# final-node.net
KiCad netlist of a schematic drawn in EAGLE
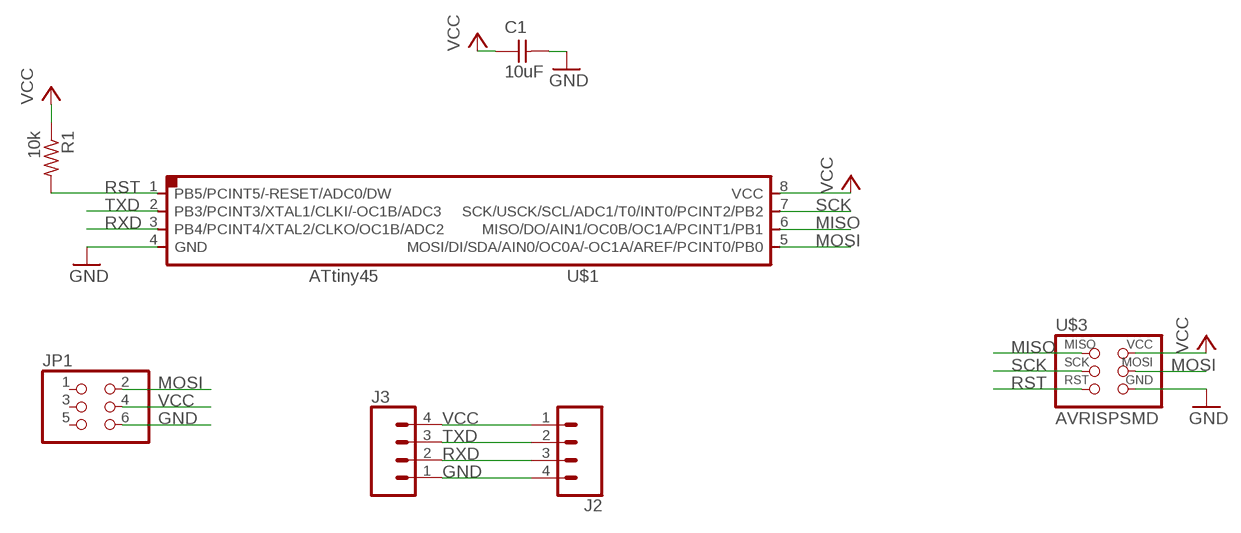
[diagram p0: schematic, sheet 1]

(export (version "E")
  (design (tool "Eeschema 10.0.6"))
  (components
    (comp (ref "C1")
      (value "10uF")
      (footprint "eagle-import:C1206FAB")
      (libsource (lib "eagle-import") (part "CAP-UNPOLARIZEDFAB"))
    )
    (comp (ref "J2")
      (value "CONN_04SMD")
      (footprint "eagle-import:1X04_SMD_RA_MALE")
      (libsource (lib "eagle-import") (part "CONN_04SMD"))
    )
    (comp (ref "J3")
      (value "CONN_04SMD")
      (footprint "eagle-import:1X04_SMD_RA_MALE")
      (libsource (lib "eagle-import") (part "CONN_04SMD"))
    )
    (comp (ref "JP1")
      (value "PINHD-2X3-SMD")
      (footprint "eagle-import:2X03SMD")
      (libsource (lib "eagle-import") (part "PINHD-2X3-SMD"))
    )
    (comp (ref "R1")
      (value "10k")
      (footprint "eagle-import:R1206FAB")
      (libsource (lib "eagle-import") (part "RES-US1206FAB"))
    )
    (comp (ref "U$1")
      (value "ATTINY45SI")
      (footprint "eagle-import:SOIC8")
      (libsource (lib "eagle-import") (part "ATTINY45SI"))
    )
    (comp (ref "U$3")
      (value "AVRISPSMD")
      (footprint "eagle-import:2X03SMD")
      (libsource (lib "eagle-import") (part "AVRISPSMD"))
    )
  )
  (nets
    (net (code "1") (name "/MISO") (class "Default")
      (node (ref "U$1") (pin "6") (pinfunction "MISO/DO/AIN1/OC0B/OC1A/PCINT1/PB1_6") (pintype "bidirectional"))
      (node (ref "U$3") (pin "1") (pinfunction "MISO_1") (pintype "passive"))
    )
    (net (code "2") (name "/MOSI") (class "Default")
      (node (ref "JP1") (pin "2") (pinfunction "2_2") (pintype "passive"))
      (node (ref "U$1") (pin "5") (pinfunction "MOSI/DI/SDA/AIN0/OC0A/-OC1A/AREF/PCINT0/PB0_5") (pintype "bidirectional"))
      (node (ref "U$3") (pin "4") (pinfunction "MOSI_4") (pintype "passive"))
    )
    (net (code "3") (name "/RST") (class "Default")
      (node (ref "R1") (pin "2") (pinfunction "2_2") (pintype "passive"))
      (node (ref "U$1") (pin "1") (pinfunction "PB5/PCINT5/-RESET/ADC0/DW_1") (pintype "bidirectional"))
      (node (ref "U$3") (pin "5") (pinfunction "RST_5") (pintype "passive"))
    )
    (net (code "4") (name "/RXD") (class "Default")
      (node (ref "J2") (pin "3") (pinfunction "3_3") (pintype "passive"))
      (node (ref "J3") (pin "2") (pinfunction "2_2") (pintype "passive"))
      (node (ref "U$1") (pin "3") (pinfunction "PB4/PCINT4/XTAL2/CLKO/OC1B/ADC2_3") (pintype "bidirectional"))
    )
    (net (code "5") (name "/SCK") (class "Default")
      (node (ref "U$1") (pin "7") (pinfunction "SCK/USCK/SCL/ADC1/T0/INT0/PCINT2/PB2_7") (pintype "bidirectional"))
      (node (ref "U$3") (pin "3") (pinfunction "SCK_3") (pintype "passive"))
    )
    (net (code "6") (name "/TXD") (class "Default")
      (node (ref "J2") (pin "2") (pinfunction "2_2") (pintype "passive"))
      (node (ref "J3") (pin "3") (pinfunction "3_3") (pintype "passive"))
      (node (ref "U$1") (pin "2") (pinfunction "PB3/PCINT3/XTAL1/CLKI/-OC1B/ADC3_2") (pintype "bidirectional"))
    )
    (net (code "7") (name "GND") (class "Default")
      (node (ref "C1") (pin "2") (pinfunction "2_2") (pintype "passive"))
      (node (ref "J2") (pin "4") (pinfunction "4_4") (pintype "passive"))
      (node (ref "J3") (pin "1") (pinfunction "1_1") (pintype "passive"))
      (node (ref "JP1") (pin "6") (pinfunction "6_6") (pintype "passive"))
      (node (ref "U$1") (pin "4") (pinfunction "GND_4") (pintype "bidirectional"))
      (node (ref "U$3") (pin "6") (pinfunction "GND_6") (pintype "passive"))
    )
    (net (code "8") (name "VCC") (class "Default")
      (node (ref "C1") (pin "1") (pinfunction "1_1") (pintype "passive"))
      (node (ref "J2") (pin "1") (pinfunction "1_1") (pintype "passive"))
      (node (ref "J3") (pin "4") (pinfunction "4_4") (pintype "passive"))
      (node (ref "JP1") (pin "4") (pinfunction "4_4") (pintype "passive"))
      (node (ref "R1") (pin "1") (pinfunction "1_1") (pintype "passive"))
      (node (ref "U$1") (pin "8") (pinfunction "VCC_8") (pintype "bidirectional"))
      (node (ref "U$3") (pin "2") (pinfunction "VCC_2") (pintype "passive"))
    )
    (net (code "9") (name "unconnected-(JP1-Pad1)") (class "Default")
      (node (ref "JP1") (pin "1") (pinfunction "1_1") (pintype "passive"))
    )
    (net (code "10") (name "unconnected-(JP1-Pad3)") (class "Default")
      (node (ref "JP1") (pin "3") (pinfunction "3_3") (pintype "passive"))
    )
    (net (code "11") (name "unconnected-(JP1-Pad5)") (class "Default")
      (node (ref "JP1") (pin "5") (pinfunction "5_5") (pintype "passive"))
    )
  )
)
